# POWER.net
KiCad netlist of a schematic drawn in Altium Designer
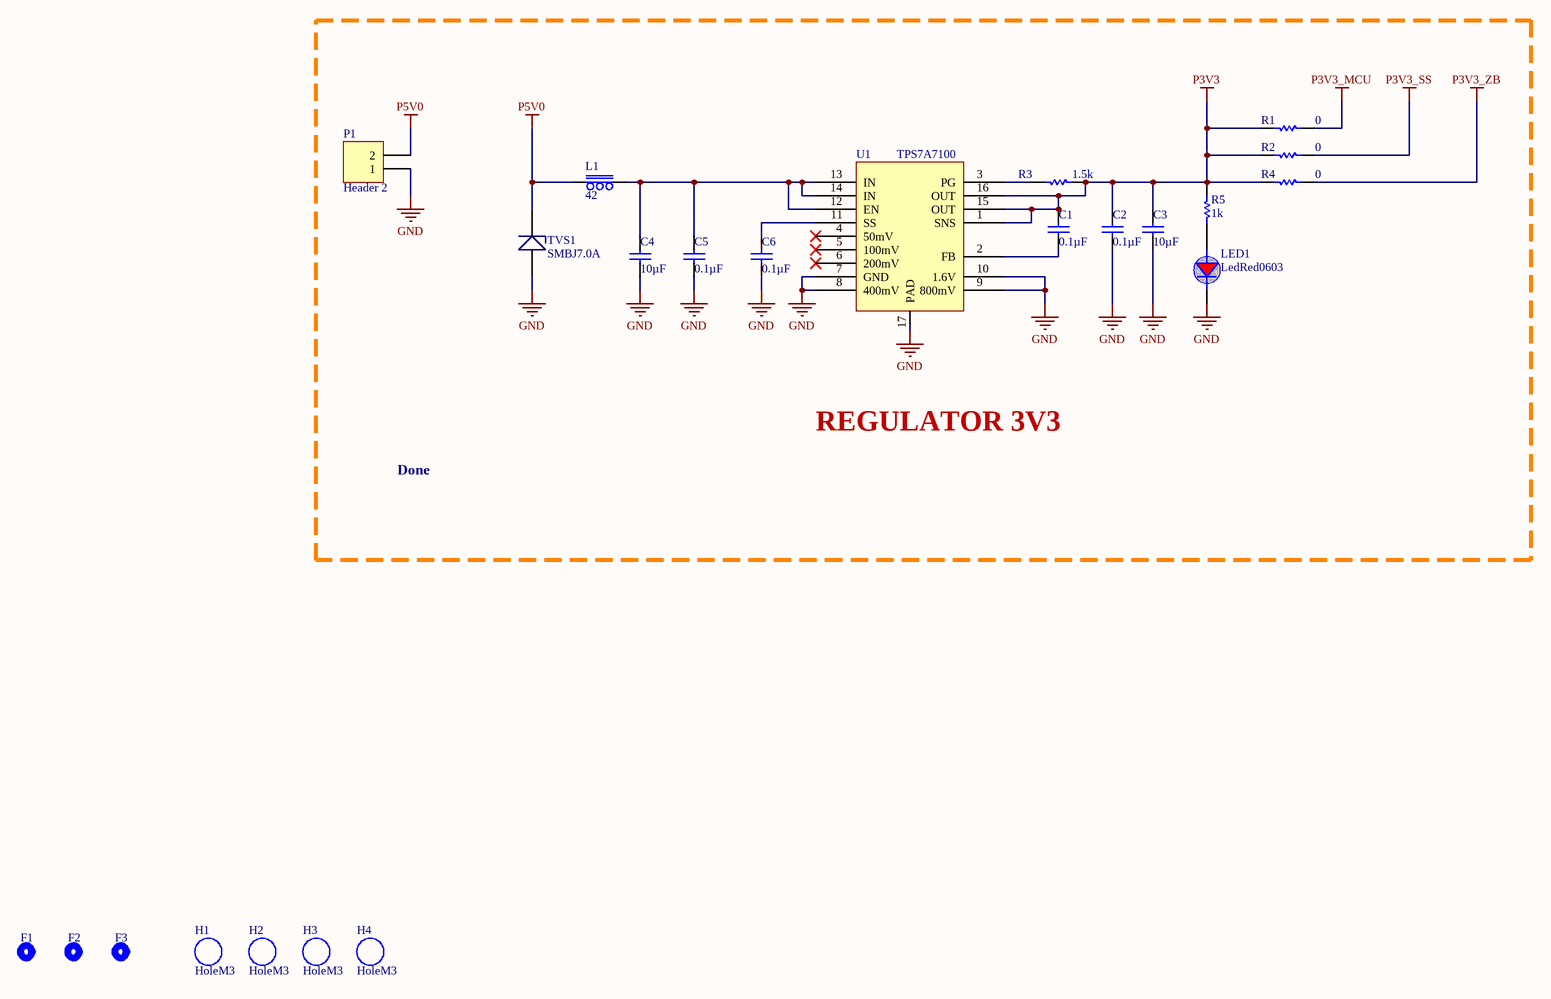
[diagram p0: POWER.SchDoc]

(export (version "E")
  (design (tool "Eeschema 10.0.6"))
  (components
    (comp (ref "C1")
      (value "0.1µF")
      (footprint "C0402M")
      (description "CAP CER 0.1UF 10V X7R 0402")
      (fields
        (field (name "MANUFACTURER") "Taiyo Yuden")
        (field (name "MANUFACTURER PART NUMBER") "LMK105B7104KVHF")
      )
      (libsource (lib "BinhLib") (part "CAP0.1u0402"))
    )
    (comp (ref "C2")
      (value "0.1µF")
      (footprint "C0402M")
      (description "CAP CER 0.1UF 10V X7R 0402")
      (fields
        (field (name "MANUFACTURER") "Taiyo Yuden")
        (field (name "MANUFACTURER PART NUMBER") "LMK105B7104KVHF")
      )
      (libsource (lib "BinhLib") (part "CAP0.1u0402"))
    )
    (comp (ref "C3")
      (value "10µF")
      (footprint "0805 cap")
      (description "CAP CER 10UF 16V X7R 0805")
      (fields
        (field (name "MANUFACTURER") "Taiyo Yuden")
        (field (name "MANUFACTURER PART NUMBER") "EMK212BB7106MG-T")
      )
      (libsource (lib "BinhLib") (part "cap10u0805"))
    )
    (comp (ref "C4")
      (value "10µF")
      (footprint "0805 cap")
      (description "CAP CER 10UF 16V X7R 0805")
      (fields
        (field (name "MANUFACTURER") "Taiyo Yuden")
        (field (name "MANUFACTURER PART NUMBER") "EMK212BB7106MG-T")
      )
      (libsource (lib "BinhLib") (part "cap10u0805"))
    )
    (comp (ref "C5")
      (value "0.1µF")
      (footprint "C0402M")
      (description "CAP CER 0.1UF 10V X7R 0402")
      (fields
        (field (name "MANUFACTURER") "Taiyo Yuden")
        (field (name "MANUFACTURER PART NUMBER") "LMK105B7104KVHF")
      )
      (libsource (lib "BinhLib") (part "CAP0.1u0402"))
    )
    (comp (ref "C6")
      (value "0.1µF")
      (footprint "C0402M")
      (description "CAP CER 0.1UF 10V X7R 0402")
      (fields
        (field (name "MANUFACTURER") "Taiyo Yuden")
        (field (name "MANUFACTURER PART NUMBER") "LMK105B7104KVHF")
      )
      (libsource (lib "BinhLib") (part "CAP0.1u0402"))
    )
    (comp (ref "F1") (value "~") (footprint "fiducials") (libsource (lib "BinhLib") (part "Fiducials")))
    (comp (ref "F2") (value "~") (footprint "fiducials") (libsource (lib "BinhLib") (part "Fiducials")))
    (comp (ref "F3") (value "~") (footprint "fiducials") (libsource (lib "BinhLib") (part "Fiducials")))
    (comp (ref "H1") (value "HoleM3") (footprint "HOLEM3via") (libsource (lib "BinhLib") (part "HoleM3")))
    (comp (ref "H2") (value "HoleM3") (footprint "HOLEM3via") (libsource (lib "BinhLib") (part "HoleM3")))
    (comp (ref "H3") (value "HoleM3") (footprint "HOLEM3via") (libsource (lib "BinhLib") (part "HoleM3")))
    (comp (ref "H4") (value "HoleM3") (footprint "HOLEM3via") (libsource (lib "BinhLib") (part "HoleM3")))
    (comp (ref "L1")
      (value "42")
      (footprint "0805F")
      (description "FERRITE BEAD 42 OHM 0805 1LN")
      (fields
        (field (name "MANUFACTURER") "Taiyo Yuden")
        (field (name "MANUFACTURER PART NUMBER") "FBMJ2125HS420-TV")
      )
      (libsource (lib "BinhLib") (part "Ferrite Bead"))
    )
    (comp (ref "LED1")
      (value "LedRed0603")
      (footprint "0603LED-RED")
      (description "LED RED CLEAR 0603 SMD")
      (fields
        (field (name "MANUFACTURER") "Everlight Electronics Co Ltd")
        (field (name "MANUFACTURER PART NUMBER") "QTLP600C7TR")
      )
      (libsource (lib "BinhLib") (part "LedRed0603"))
    )
    (comp (ref "P1")
      (value "Header 2")
      (footprint "HED2T")
      (description "Header, 2-Pin")
      (fields (field (name "PUBLISHER") "Altium Limited"))
      (libsource (lib "BinhLib") (part "Header 2"))
    )
    (comp (ref "R1")
      (value "0")
      (footprint "R0805M")
      (description "RES SMD 0.0 OHM JUMPER 1/8W 0805")
      (fields
        (field (name "MANUFACTURER") "Panasonic Electronic Components")
        (field (name "MANUFACTURER PART NUMBER") "ERJ-6GEY0R00V")
      )
      (libsource (lib "BinhLib") (part "RES00805"))
    )
    (comp (ref "R2")
      (value "0")
      (footprint "R0805M")
      (description "RES SMD 0.0 OHM JUMPER 1/8W 0805")
      (fields
        (field (name "MANUFACTURER") "Panasonic Electronic Components")
        (field (name "MANUFACTURER PART NUMBER") "ERJ-6GEY0R00V")
      )
      (libsource (lib "BinhLib") (part "RES00805"))
    )
    (comp (ref "R3")
      (value "1.5k")
      (footprint "R0603M")
      (description "RES SMD 1.5K OHM 1% 1/10W 0603")
      (fields
        (field (name "MANUFACTURER") "Panasonic Electronic Components")
        (field (name "MANUFACTURER PART NUMBER") "ERJ-3EKF1501V")
      )
      (libsource (lib "BinhLib") (part "RES1k50603"))
    )
    (comp (ref "R4")
      (value "0")
      (footprint "R0805M")
      (description "RES SMD 0.0 OHM JUMPER 1/8W 0805")
      (fields
        (field (name "MANUFACTURER") "Panasonic Electronic Components")
        (field (name "MANUFACTURER PART NUMBER") "ERJ-6GEY0R00V")
      )
      (libsource (lib "BinhLib") (part "RES00805"))
    )
    (comp (ref "R5")
      (value "1k")
      (footprint "R0603M")
      (description "RES SMD 1K OHM 1% 1/10W 0603")
      (fields
        (field (name "MANUFACTURER") "Panasonic Electronic Components")
        (field (name "MANUFACTURER PART NUMBER") "ERJ-3EKF1001V")
      )
      (libsource (lib "BinhLib") (part "RES1k0603"))
    )
    (comp (ref "TVS1")
      (value "SMBJ7.0A")
      (footprint "DIOM4436X26N")
      (description "TVS DIODE 7V 12V DO214AA")
      (libsource (lib "SmartHome") (part "TVS"))
    )
    (comp (ref "U1")
      (value "TPS7A7100")
      (footprint "QFN16")
      (description "IC REG LDO FIX/ADJ 1A 16QFN")
      (fields
        (field (name "MANUFACTURER") "Texas Instruments")
        (field (name "MANUFACTURER PART NUMBER") "TPS7A7100RGTR")
      )
      (libsource (lib "BinhLib") (part "TPS7A7100"))
    )
  )
  (nets
    (net (code "1") (name "GND") (class "Default")
      (node (ref "C2") (pin "1") (pintype "passive"))
      (node (ref "C3") (pin "1") (pintype "passive"))
      (node (ref "C4") (pin "1") (pintype "passive"))
      (node (ref "C5") (pin "1") (pintype "passive"))
      (node (ref "C6") (pin "1") (pintype "passive"))
      (node (ref "LED1") (pin "2") (pinfunction "Katot_2") (pintype "passive"))
      (node (ref "P1") (pin "1") (pinfunction "1_1") (pintype "passive"))
      (node (ref "TVS1") (pin "1") (pinfunction "1_1") (pintype "passive"))
      (node (ref "U1") (pin "10") (pinfunction "1.6V_10") (pintype "passive"))
      (node (ref "U1") (pin "17") (pinfunction "PAD_17") (pintype "passive"))
      (node (ref "U1") (pin "7") (pinfunction "GND_7") (pintype "power_in"))
      (node (ref "U1") (pin "8") (pinfunction "400mV_8") (pintype "passive"))
      (node (ref "U1") (pin "9") (pinfunction "800mV_9") (pintype "passive"))
    )
    (net (code "2") (name "Net-(LED1-anot)") (class "Default")
      (node (ref "LED1") (pin "1") (pinfunction "anot_1") (pintype "passive"))
      (node (ref "R5") (pin "1") (pinfunction "1_1") (pintype "passive"))
    )
    (net (code "3") (name "Net-(U1-EN)") (class "Default")
      (node (ref "C4") (pin "2") (pintype "passive"))
      (node (ref "C5") (pin "2") (pintype "passive"))
      (node (ref "L1") (pin "2") (pintype "passive"))
      (node (ref "U1") (pin "12") (pinfunction "EN_12") (pintype "passive"))
      (node (ref "U1") (pin "13") (pinfunction "IN_13") (pintype "passive"))
      (node (ref "U1") (pin "14") (pinfunction "IN_14") (pintype "passive"))
    )
    (net (code "4") (name "Net-(U1-FB)") (class "Default")
      (node (ref "C1") (pin "1") (pintype "passive"))
      (node (ref "U1") (pin "2") (pinfunction "FB_2") (pintype "passive"))
    )
    (net (code "5") (name "Net-(U1-PG)") (class "Default")
      (node (ref "R3") (pin "1") (pinfunction "1_1") (pintype "passive"))
      (node (ref "U1") (pin "3") (pinfunction "PG_3") (pintype "passive"))
    )
    (net (code "6") (name "Net-(U1-SS)") (class "Default")
      (node (ref "C6") (pin "2") (pintype "passive"))
      (node (ref "U1") (pin "11") (pinfunction "SS_11") (pintype "passive"))
    )
    (net (code "7") (name "P3V3") (class "Default")
      (node (ref "C1") (pin "2") (pintype "passive"))
      (node (ref "C2") (pin "2") (pintype "passive"))
      (node (ref "C3") (pin "2") (pintype "passive"))
      (node (ref "R1") (pin "1") (pinfunction "1_1") (pintype "passive"))
      (node (ref "R2") (pin "1") (pinfunction "1_1") (pintype "passive"))
      (node (ref "R3") (pin "2") (pinfunction "2_2") (pintype "passive"))
      (node (ref "R4") (pin "1") (pinfunction "1_1") (pintype "passive"))
      (node (ref "R5") (pin "2") (pinfunction "2_2") (pintype "passive"))
      (node (ref "U1") (pin "1") (pinfunction "SNS_1") (pintype "passive"))
      (node (ref "U1") (pin "15") (pinfunction "OUT_15") (pintype "passive"))
      (node (ref "U1") (pin "16") (pinfunction "OUT_16") (pintype "passive"))
    )
    (net (code "8") (name "P3V3_MCU") (class "Default")
      (node (ref "R1") (pin "2") (pinfunction "2_2") (pintype "passive"))
    )
    (net (code "9") (name "P3V3_SS") (class "Default")
      (node (ref "R2") (pin "2") (pinfunction "2_2") (pintype "passive"))
    )
    (net (code "10") (name "P3V3_ZB") (class "Default")
      (node (ref "R4") (pin "2") (pinfunction "2_2") (pintype "passive"))
    )
    (net (code "11") (name "P5V0") (class "Default")
      (node (ref "L1") (pin "1") (pintype "passive"))
      (node (ref "P1") (pin "2") (pinfunction "2_2") (pintype "passive"))
      (node (ref "TVS1") (pin "2") (pinfunction "2_2") (pintype "passive"))
    )
    (net (code "12") (name "unconnected-(U1-50mV-Pad4)") (class "Default")
      (node (ref "U1") (pin "4") (pinfunction "50mV_4") (pintype "passive+no_connect"))
    )
    (net (code "13") (name "unconnected-(U1-100mV-Pad5)") (class "Default")
      (node (ref "U1") (pin "5") (pinfunction "100mV_5") (pintype "passive+no_connect"))
    )
    (net (code "14") (name "unconnected-(U1-200mV-Pad6)") (class "Default")
      (node (ref "U1") (pin "6") (pinfunction "200mV_6") (pintype "passive+no_connect"))
    )
  )
)
